# LVDS_Driver_Subsystem.net
KiCad netlist of a schematic drawn in Altium Designer
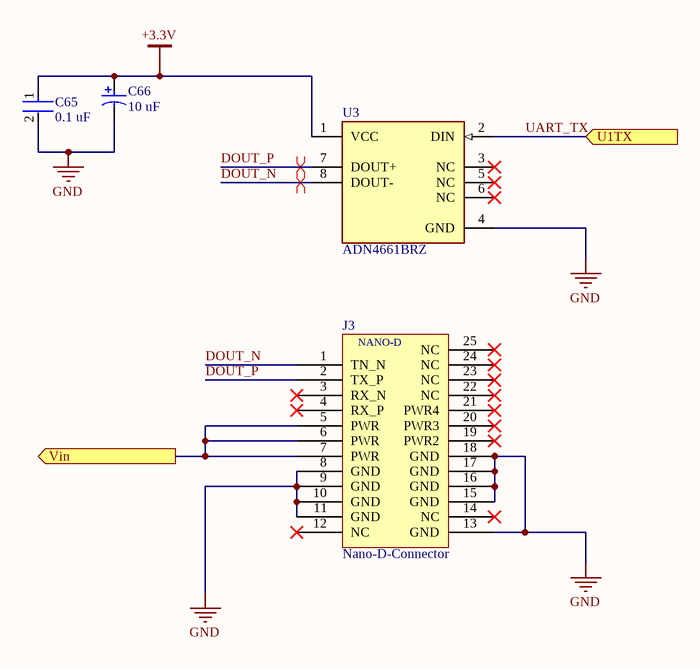
[diagram p0: LVDS_Driver_Subsystem.SchDoc]

(export (version "E")
  (design (tool "Eeschema 10.0.6"))
  (components
    (comp (ref "C65")
      (value "0.1 uF")
      (footprint "FP-CC0603-DA-MFG")
      (description "CAP CER 0.1UF 16V X7R 0603 CC0603KRX7R7BB104")
      (fields
        (field (name "OCTOPART") "https://octopart.com/cc0603krx7r7bb104-yageo-192941")
        (field (name "TOLERANCE") "0.1")
      )
      (libsource (lib "Altium Content Vault") (part "11868f565c42a9108669ba33697ecf6"))
    )
    (comp (ref "C66")
      (value "10 uF")
      (footprint "VISH-TR8-M_L")
      (fields (field (name "TOLERANCE") "±20%") (field (name "MANUFACTURER") "Vishay"))
      (libsource (lib "Altium Content Vault") (part "CAP-P-2"))
    )
    (comp (ref "J3")
      (value "Nano-D-Connector")
      (footprint "A28400-025")
      (libsource (lib "Connectors") (part "Nano-D-Connector"))
    )
    (comp (ref "U3")
      (value "ADN4661BRZ")
      (footprint "FP-R-8-IPC_A")
      (description "IC DRIVER 1/0 8SOIC")
      (libsource (lib "Altium Content Vault") (part "f8d6ee1c26474eb5cd2f3fb550722cd"))
    )
  )
  (nets
    (net (code "1") (name "+3.3V") (class "Default")
      (node (ref "C65") (pin "1") (pinfunction "1_1") (pintype "passive"))
      (node (ref "C66") (pin "1") (pinfunction "1_1") (pintype "passive"))
      (node (ref "U3") (pin "1") (pinfunction "VCC_1") (pintype "power_in"))
    )
    (net (code "2") (name "/DOUT_N") (class "Default")
      (node (ref "J3") (pin "1") (pinfunction "TN_N_1") (pintype "passive"))
      (node (ref "U3") (pin "8") (pinfunction "DOUT-_8") (pintype "passive"))
    )
    (net (code "3") (name "/DOUT_P") (class "Default")
      (node (ref "J3") (pin "2") (pinfunction "TX_P_2") (pintype "passive"))
      (node (ref "U3") (pin "7") (pinfunction "DOUT+_7") (pintype "passive"))
    )
    (net (code "4") (name "/UART_TX") (class "Default")
      (node (ref "U3") (pin "2") (pinfunction "DIN_2") (pintype "input"))
    )
    (net (code "5") (name "/Vin") (class "Default")
      (node (ref "J3") (pin "5") (pinfunction "PWR_5") (pintype "passive"))
      (node (ref "J3") (pin "6") (pinfunction "PWR_6") (pintype "passive"))
      (node (ref "J3") (pin "7") (pinfunction "PWR_7") (pintype "passive"))
    )
    (net (code "6") (name "GND") (class "Default")
      (node (ref "C65") (pin "2") (pinfunction "2_2") (pintype "passive"))
      (node (ref "C66") (pin "2") (pinfunction "2_2") (pintype "passive"))
      (node (ref "J3") (pin "10") (pinfunction "GND_10") (pintype "passive"))
      (node (ref "J3") (pin "11") (pinfunction "GND_11") (pintype "passive"))
      (node (ref "J3") (pin "13") (pinfunction "GND_13") (pintype "passive"))
      (node (ref "J3") (pin "15") (pinfunction "GND_15") (pintype "passive"))
      (node (ref "J3") (pin "16") (pinfunction "GND_16") (pintype "passive"))
      (node (ref "J3") (pin "17") (pinfunction "GND_17") (pintype "passive"))
      (node (ref "J3") (pin "18") (pinfunction "GND_18") (pintype "passive"))
      (node (ref "J3") (pin "8") (pinfunction "GND_8") (pintype "passive"))
      (node (ref "J3") (pin "9") (pinfunction "GND_9") (pintype "passive"))
      (node (ref "U3") (pin "4") (pinfunction "GND_4") (pintype "power_in"))
    )
    (net (code "7") (name "unconnected-(J3-NC-Pad12)") (class "Default")
      (node (ref "J3") (pin "12") (pinfunction "NC_12") (pintype "passive+no_connect"))
    )
    (net (code "8") (name "unconnected-(J3-NC-Pad14)") (class "Default")
      (node (ref "J3") (pin "14") (pinfunction "NC_14") (pintype "passive+no_connect"))
    )
    (net (code "9") (name "unconnected-(J3-NC-Pad22)") (class "Default")
      (node (ref "J3") (pin "22") (pinfunction "NC_22") (pintype "passive+no_connect"))
    )
    (net (code "10") (name "unconnected-(J3-NC-Pad23)") (class "Default")
      (node (ref "J3") (pin "23") (pinfunction "NC_23") (pintype "passive+no_connect"))
    )
    (net (code "11") (name "unconnected-(J3-NC-Pad24)") (class "Default")
      (node (ref "J3") (pin "24") (pinfunction "NC_24") (pintype "passive+no_connect"))
    )
    (net (code "12") (name "unconnected-(J3-NC-Pad25)") (class "Default")
      (node (ref "J3") (pin "25") (pinfunction "NC_25") (pintype "passive+no_connect"))
    )
    (net (code "13") (name "unconnected-(J3-PWR2-Pad19)") (class "Default")
      (node (ref "J3") (pin "19") (pinfunction "PWR2_19") (pintype "passive+no_connect"))
    )
    (net (code "14") (name "unconnected-(J3-PWR3-Pad20)") (class "Default")
      (node (ref "J3") (pin "20") (pinfunction "PWR3_20") (pintype "passive+no_connect"))
    )
    (net (code "15") (name "unconnected-(J3-PWR4-Pad21)") (class "Default")
      (node (ref "J3") (pin "21") (pinfunction "PWR4_21") (pintype "passive+no_connect"))
    )
    (net (code "16") (name "unconnected-(J3-RX_N-Pad3)") (class "Default")
      (node (ref "J3") (pin "3") (pinfunction "RX_N_3") (pintype "passive+no_connect"))
    )
    (net (code "17") (name "unconnected-(J3-RX_P-Pad4)") (class "Default")
      (node (ref "J3") (pin "4") (pinfunction "RX_P_4") (pintype "passive+no_connect"))
    )
    (net (code "18") (name "unconnected-(U3-NC-Pad3)") (class "Default")
      (node (ref "U3") (pin "3") (pinfunction "NC_3") (pintype "passive+no_connect"))
    )
    (net (code "19") (name "unconnected-(U3-NC-Pad5)") (class "Default")
      (node (ref "U3") (pin "5") (pinfunction "NC_5") (pintype "passive+no_connect"))
    )
    (net (code "20") (name "unconnected-(U3-NC-Pad6)") (class "Default")
      (node (ref "U3") (pin "6") (pinfunction "NC_6") (pintype "passive+no_connect"))
    )
  )
)
